# WL-RF-CONN.net
KiCad netlist of a schematic drawn in Altium Designer
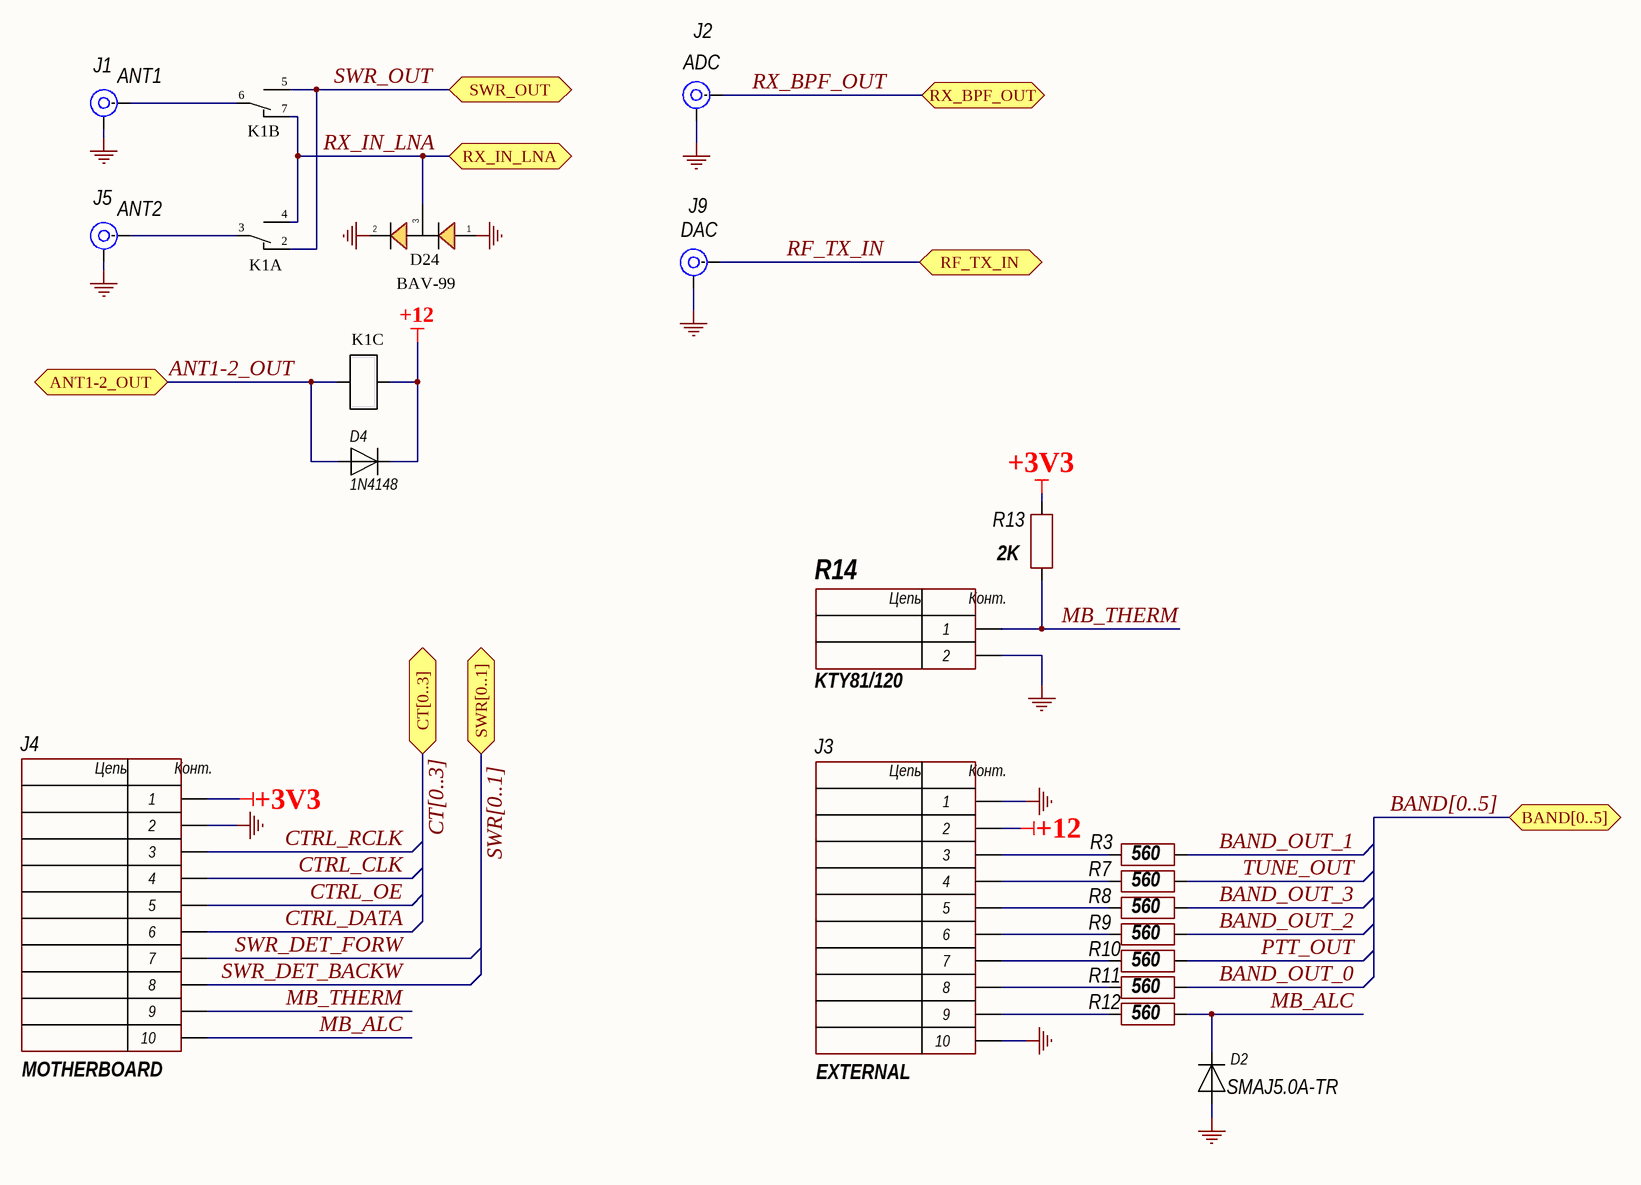
[diagram p0: WL-RF-CONN.SchDoc]

(export (version "E")
  (design (tool "Eeschema 10.0.6"))
  (components
    (comp (ref "D2")
      (value "SMAJ5.0A-TR")
      (footprint "standard:SOD123")
      (libsource (lib "Diods") (part "Diod"))
    )
    (comp (ref "D4") (value "1N4148") (footprint "standard:SOD123") (libsource (lib "Diods") (part "Diod")))
    (comp (ref "D24")
      (value "BAV-99")
      (footprint "standard:SOT23_132")
      (libsource (lib "Analog") (part "BAV-99"))
    )
    (comp (ref "J1")
      (value "ANT1")
      (footprint "custom:CON: SMA")
      (description "RF")
      (libsource (lib "Connectors") (part "SMA"))
    )
    (comp (ref "J2")
      (value "ADC")
      (footprint "custom:CON: SMA")
      (description "RF")
      (libsource (lib "Connectors") (part "SMA"))
    )
    (comp (ref "J3")
      (value "EXTERNAL")
      (footprint "custom:CON: 0533751010")
      (libsource (lib "Connectors") (part "10-Connector"))
    )
    (comp (ref "J4")
      (value "MOTHERBOARD")
      (footprint "custom:CON: 0533751010")
      (libsource (lib "Connectors") (part "10-Connector"))
    )
    (comp (ref "J5")
      (value "ANT2")
      (footprint "custom:CON: SMA")
      (description "RF")
      (libsource (lib "Connectors") (part "SMA"))
    )
    (comp (ref "J9")
      (value "DAC")
      (footprint "custom:CON: SMA")
      (description "RF")
      (libsource (lib "Connectors") (part "SMA"))
    )
    (comp (ref "K1") (value "IM06") (footprint "IMG06") (libsource (lib "") (part "IM06-1_1")))
    (comp (ref "R3") (value "560") (footprint "standard:CH0805R") (libsource (lib "") (part "Resistor_1")))
    (comp (ref "R7") (value "560") (footprint "standard:CH0805R") (libsource (lib "") (part "Resistor_1")))
    (comp (ref "R8") (value "560") (footprint "standard:CH0805R") (libsource (lib "") (part "Resistor_1")))
    (comp (ref "R9") (value "560") (footprint "standard:CH0805R") (libsource (lib "") (part "Resistor_1")))
    (comp (ref "R10") (value "560") (footprint "standard:CH0805R") (libsource (lib "") (part "Resistor_1")))
    (comp (ref "R11") (value "560") (footprint "standard:CH0805R") (libsource (lib "") (part "Resistor_1")))
    (comp (ref "R12") (value "560") (footprint "standard:CH0805R") (libsource (lib "") (part "Resistor_1")))
    (comp (ref "R13")
      (value "2K")
      (footprint "standard:CH0805R")
      (libsource (lib "Discrete") (part "Resistor"))
    )
    (comp (ref "R14")
      (value "KTY81/120")
      (footprint "custom:CON: CWF-2")
      (libsource (lib "Connectors") (part "2-Connector"))
    )
  )
  (nets
    (net (code "13") (name "+3V3") (class "Default")
      (node (ref "J4") (pin "1") (pinfunction "1_1") (pintype "passive"))
      (node (ref "R13") (pin "2") (pinfunction "2_2") (pintype "passive"))
    )
    (net (code "14") (name "+12") (class "Default")
      (node (ref "D4") (pin "2") (pinfunction "2_2") (pintype "passive"))
      (node (ref "J3") (pin "2") (pinfunction "2_2") (pintype "passive"))
      (node (ref "K1") (pin "8") (pintype "passive"))
    )
    (net (code "15") (name "/ANT1-2_OUT") (class "Default")
      (node (ref "D4") (pin "1") (pinfunction "1_1") (pintype "passive"))
      (node (ref "K1") (pin "1") (pintype "passive"))
    )
    (net (code "17") (name "/BAND_OUT_0") (class "Default")
      (node (ref "R11") (pin "1") (pinfunction "1_1") (pintype "passive"))
    )
    (net (code "18") (name "/BAND_OUT_1") (class "Default")
      (node (ref "R3") (pin "1") (pinfunction "1_1") (pintype "passive"))
    )
    (net (code "19") (name "/BAND_OUT_2") (class "Default")
      (node (ref "R9") (pin "1") (pinfunction "1_1") (pintype "passive"))
    )
    (net (code "20") (name "/BAND_OUT_3") (class "Default")
      (node (ref "R8") (pin "1") (pinfunction "1_1") (pintype "passive"))
    )
    (net (code "21") (name "/CTRL_CLK") (class "Default")
      (node (ref "J4") (pin "4") (pinfunction "4_4") (pintype "power_in"))
    )
    (net (code "22") (name "/CTRL_DATA") (class "Default")
      (node (ref "J4") (pin "6") (pinfunction "6_6") (pintype "power_in"))
    )
    (net (code "23") (name "/CTRL_OE") (class "Default")
      (node (ref "J4") (pin "5") (pinfunction "5_5") (pintype "power_in"))
    )
    (net (code "24") (name "/CTRL_RCLK") (class "Default")
      (node (ref "J4") (pin "3") (pinfunction "3_3") (pintype "power_in"))
    )
    (net (code "26") (name "/MB_ALC") (class "Default")
      (node (ref "D2") (pin "2") (pinfunction "2_2") (pintype "passive"))
      (node (ref "J4") (pin "10") (pinfunction "10_10") (pintype "power_in"))
      (node (ref "R12") (pin "1") (pinfunction "1_1") (pintype "passive"))
    )
    (net (code "27") (name "/MB_THERM") (class "Default")
      (node (ref "J4") (pin "9") (pinfunction "9_9") (pintype "power_in"))
      (node (ref "R13") (pin "1") (pinfunction "1_1") (pintype "passive"))
      (node (ref "R14") (pin "1") (pinfunction "1_1") (pintype "passive"))
    )
    (net (code "28") (name "/PTT_OUT") (class "Default")
      (node (ref "R10") (pin "1") (pinfunction "1_1") (pintype "passive"))
    )
    (net (code "29") (name "/RF_TX_IN") (class "Default")
      (node (ref "J9") (pin "1") (pinfunction "IN_1") (pintype "passive"))
    )
    (net (code "30") (name "/RX_BPF_OUT") (class "Default")
      (node (ref "J2") (pin "1") (pinfunction "IN_1") (pintype "passive"))
    )
    (net (code "31") (name "/RX_IN_LNA") (class "Default")
      (node (ref "D24") (pin "3") (pinfunction "3_3") (pintype "passive"))
      (node (ref "K1") (pin "4") (pintype "passive"))
      (node (ref "K1") (pin "7") (pintype "passive"))
    )
    (net (code "33") (name "/SWR_DET_BACKW") (class "Default")
      (node (ref "J4") (pin "8") (pinfunction "8_8") (pintype "power_in"))
    )
    (net (code "34") (name "/SWR_DET_FORW") (class "Default")
      (node (ref "J4") (pin "7") (pinfunction "7_7") (pintype "power_in"))
    )
    (net (code "35") (name "/SWR_OUT") (class "Default")
      (node (ref "K1") (pin "2") (pintype "passive"))
      (node (ref "K1") (pin "5") (pintype "passive"))
    )
    (net (code "36") (name "/TUNE_OUT") (class "Default")
      (node (ref "R7") (pin "1") (pinfunction "1_1") (pintype "passive"))
    )
    (net (code "37") (name "GND") (class "Default")
      (node (ref "D2") (pin "1") (pinfunction "1_1") (pintype "passive"))
      (node (ref "D24") (pin "1") (pinfunction "1_1") (pintype "passive"))
      (node (ref "D24") (pin "2") (pinfunction "1_2") (pintype "passive"))
      (node (ref "J1") (pin "2") (pinfunction "IN_2") (pintype "passive"))
      (node (ref "J2") (pin "2") (pinfunction "IN_2") (pintype "passive"))
      (node (ref "J3") (pin "1") (pinfunction "1_1") (pintype "passive"))
      (node (ref "J3") (pin "10") (pinfunction "10_10") (pintype "power_in"))
      (node (ref "J4") (pin "2") (pinfunction "2_2") (pintype "passive"))
      (node (ref "J5") (pin "2") (pinfunction "IN_2") (pintype "passive"))
      (node (ref "J9") (pin "2") (pinfunction "IN_2") (pintype "passive"))
      (node (ref "R14") (pin "2") (pinfunction "2_2") (pintype "passive"))
    )
    (net (code "38") (name "Net-(J1-IN-Pad1)") (class "Default")
      (node (ref "J1") (pin "1") (pinfunction "IN_1") (pintype "passive"))
      (node (ref "K1") (pin "6") (pintype "passive"))
    )
    (net (code "39") (name "Net-(J3-Pad3)") (class "Default")
      (node (ref "J3") (pin "3") (pinfunction "3_3") (pintype "power_in"))
      (node (ref "R3") (pin "2") (pinfunction "2_2") (pintype "passive"))
    )
    (net (code "40") (name "Net-(J3-Pad4)") (class "Default")
      (node (ref "J3") (pin "4") (pinfunction "4_4") (pintype "power_in"))
      (node (ref "R7") (pin "2") (pinfunction "2_2") (pintype "passive"))
    )
    (net (code "41") (name "Net-(J3-Pad5)") (class "Default")
      (node (ref "J3") (pin "5") (pinfunction "5_5") (pintype "power_in"))
      (node (ref "R8") (pin "2") (pinfunction "2_2") (pintype "passive"))
    )
    (net (code "42") (name "Net-(J3-Pad6)") (class "Default")
      (node (ref "J3") (pin "6") (pinfunction "6_6") (pintype "power_in"))
      (node (ref "R9") (pin "2") (pinfunction "2_2") (pintype "passive"))
    )
    (net (code "43") (name "Net-(J3-Pad7)") (class "Default")
      (node (ref "J3") (pin "7") (pinfunction "7_7") (pintype "power_in"))
      (node (ref "R10") (pin "2") (pinfunction "2_2") (pintype "passive"))
    )
    (net (code "44") (name "Net-(J3-Pad8)") (class "Default")
      (node (ref "J3") (pin "8") (pinfunction "8_8") (pintype "power_in"))
      (node (ref "R11") (pin "2") (pinfunction "2_2") (pintype "passive"))
    )
    (net (code "45") (name "Net-(J3-Pad9)") (class "Default")
      (node (ref "J3") (pin "9") (pinfunction "9_9") (pintype "power_in"))
      (node (ref "R12") (pin "2") (pinfunction "2_2") (pintype "passive"))
    )
    (net (code "46") (name "Net-(J5-IN-Pad1)") (class "Default")
      (node (ref "J5") (pin "1") (pinfunction "IN_1") (pintype "passive"))
      (node (ref "K1") (pin "3") (pintype "passive"))
    )
  )
)
